# Encoder.net
KiCad netlist of a schematic drawn in Altium Designer
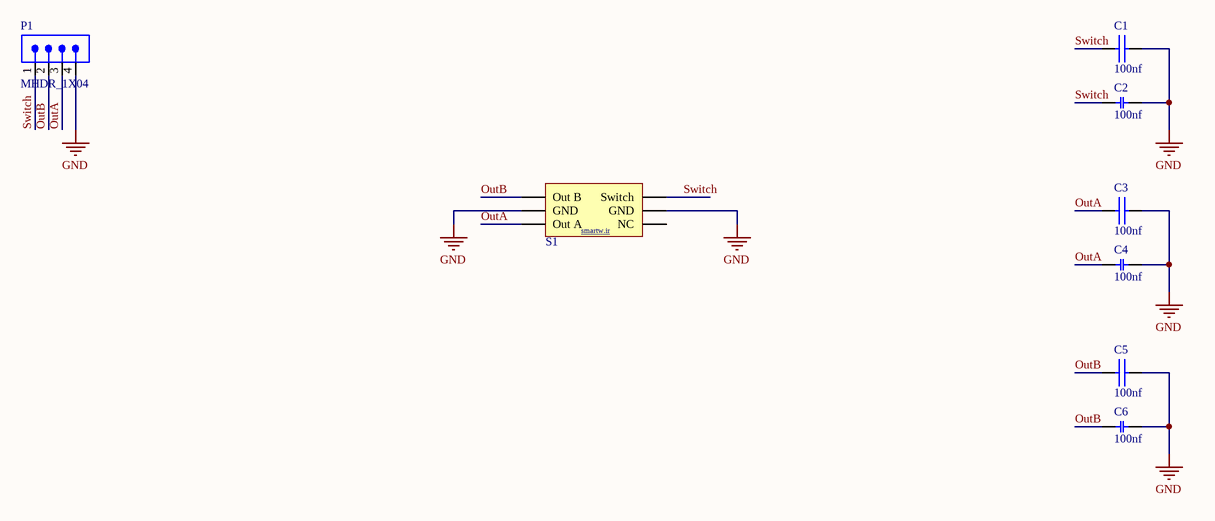
[diagram p0: Encoder.SchDoc]

(export (version "E")
  (design (tool "Eeschema 10.0.6"))
  (components
    (comp (ref "C1")
      (value "100nf")
      (footprint "C_CER_M5")
      (description "Capacitor Ceramic THD")
      (libsource (lib "Capacitor") (part "Capacitor Ceramic THD"))
    )
    (comp (ref "C2")
      (value "100nf")
      (footprint "C1206")
      (description "Capacitor C SMD 1206")
      (libsource (lib "Capacitor") (part "Capacitor C SMD 1206"))
    )
    (comp (ref "C3")
      (value "100nf")
      (footprint "C_CER_M5")
      (description "Capacitor Ceramic THD")
      (libsource (lib "Capacitor") (part "Capacitor Ceramic THD"))
    )
    (comp (ref "C4")
      (value "100nf")
      (footprint "C1206")
      (description "Capacitor C SMD 1206")
      (libsource (lib "Capacitor") (part "Capacitor C SMD 1206"))
    )
    (comp (ref "C5")
      (value "100nf")
      (footprint "C_CER_M5")
      (description "Capacitor Ceramic THD")
      (libsource (lib "Capacitor") (part "Capacitor Ceramic THD"))
    )
    (comp (ref "C6")
      (value "100nf")
      (footprint "C1206")
      (description "Capacitor C SMD 1206")
      (libsource (lib "Capacitor") (part "Capacitor C SMD 1206"))
    )
    (comp (ref "P1")
      (value "MHDR_1X04")
      (footprint "MHDR1X04-254P")
      (description "Male Header 1X04")
      (libsource (lib "Header") (part "MHDR_1X04"))
    )
    (comp (ref "S1") (value "Encoder") (footprint "Encoder") (libsource (lib "Switch") (part "Encoder")))
  )
  (nets
    (net (code "1") (name "/OutA") (class "Default")
      (node (ref "C3") (pin "1") (pinfunction "+_1") (pintype "passive"))
      (node (ref "C4") (pin "1") (pinfunction "1_1") (pintype "passive"))
      (node (ref "P1") (pin "3") (pinfunction "3_3") (pintype "passive"))
      (node (ref "S1") (pin "1") (pinfunction "Out_A_1") (pintype "passive"))
    )
    (net (code "2") (name "/OutB") (class "Default")
      (node (ref "C5") (pin "1") (pinfunction "+_1") (pintype "passive"))
      (node (ref "C6") (pin "1") (pinfunction "1_1") (pintype "passive"))
      (node (ref "P1") (pin "2") (pinfunction "2_2") (pintype "passive"))
      (node (ref "S1") (pin "2") (pinfunction "Out_B_2") (pintype "passive"))
    )
    (net (code "3") (name "/Switch") (class "Default")
      (node (ref "C1") (pin "1") (pinfunction "+_1") (pintype "passive"))
      (node (ref "C2") (pin "1") (pinfunction "1_1") (pintype "passive"))
      (node (ref "P1") (pin "1") (pinfunction "1_1") (pintype "passive"))
      (node (ref "S1") (pin "5") (pinfunction "Switch_5") (pintype "passive"))
    )
    (net (code "4") (name "GND") (class "Default")
      (node (ref "C1") (pin "2") (pinfunction "-_2") (pintype "passive"))
      (node (ref "C2") (pin "2") (pinfunction "2_2") (pintype "passive"))
      (node (ref "C3") (pin "2") (pinfunction "-_2") (pintype "passive"))
      (node (ref "C4") (pin "2") (pinfunction "2_2") (pintype "passive"))
      (node (ref "C5") (pin "2") (pinfunction "-_2") (pintype "passive"))
      (node (ref "C6") (pin "2") (pinfunction "2_2") (pintype "passive"))
      (node (ref "P1") (pin "4") (pinfunction "4_4") (pintype "passive"))
      (node (ref "S1") (pin "3") (pinfunction "GND_3") (pintype "passive"))
      (node (ref "S1") (pin "4") (pinfunction "GND_4") (pintype "passive"))
    )
    (net (code "5") (name "unconnected-(S1-NC-Pad0)") (class "Default")
      (node (ref "S1") (pin "0") (pinfunction "NC_0") (pintype "passive"))
    )
  )
)
